# OPBS-Dynamo.net
KiCad netlist of a schematic drawn in EAGLE
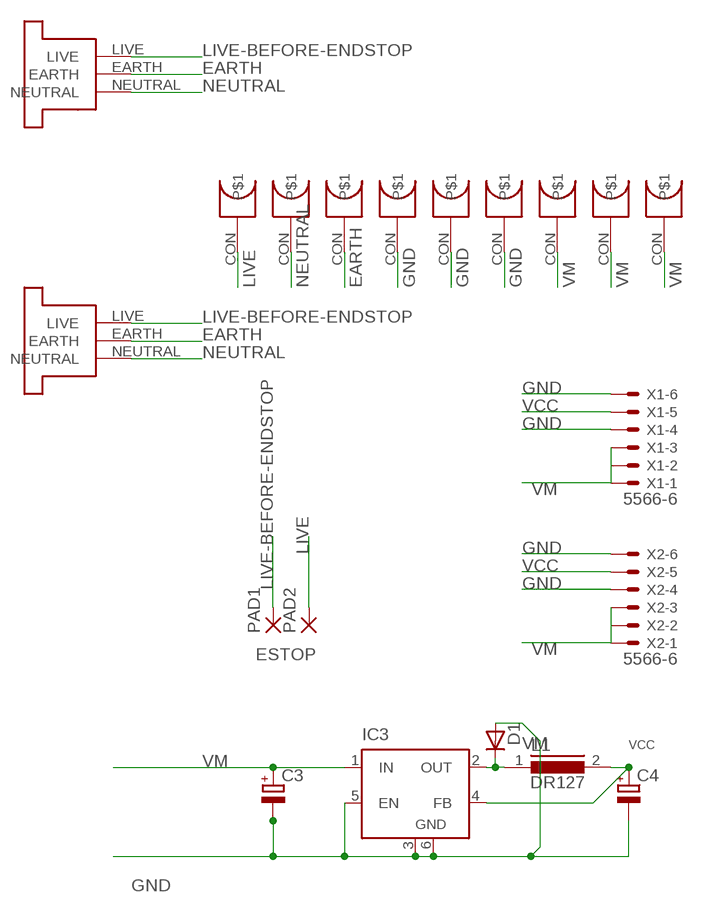
[diagram p0: schematic, sheet 1]

(export (version "E")
  (design (tool "Eeschema 10.0.6"))
  (components
    (comp (ref "C3")
      (value "CPOL-EUE")
      (footprint "eagle-import:PANASONIC_E")
      (libsource (lib "eagle-import") (part "CPOL-EUE"))
    )
    (comp (ref "C4")
      (value "CPOL-EUE")
      (footprint "eagle-import:PANASONIC_E")
      (libsource (lib "eagle-import") (part "CPOL-EUE"))
    )
    (comp (ref "D1")
      (value "D-SOD-87")
      (footprint "eagle-import:SOD87")
      (libsource (lib "eagle-import") (part "D-SOD-87"))
    )
    (comp (ref "EARTH")
      (value "SLIDEINSCREW9.53")
      (footprint "eagle-import:SLIDEINSCREW")
      (libsource (lib "eagle-import") (part "SLIDEINSCREW9.53"))
    )
    (comp (ref "GND1")
      (value "SLIDEINSCREW9.53")
      (footprint "eagle-import:SLIDEINSCREW")
      (libsource (lib "eagle-import") (part "SLIDEINSCREW9.53"))
    )
    (comp (ref "GND2")
      (value "SLIDEINSCREW9.53")
      (footprint "eagle-import:SLIDEINSCREW")
      (libsource (lib "eagle-import") (part "SLIDEINSCREW9.53"))
    )
    (comp (ref "GND3")
      (value "SLIDEINSCREW9.53")
      (footprint "eagle-import:SLIDEINSCREW")
      (libsource (lib "eagle-import") (part "SLIDEINSCREW9.53"))
    )
    (comp (ref "IC3")
      (value "LM2596S")
      (footprint "eagle-import:TO263-5")
      (libsource (lib "eagle-import") (part "LM2596S"))
    )
    (comp (ref "L1")
      (value "DR127")
      (footprint "eagle-import:DR127")
      (libsource (lib "eagle-import") (part "DR127"))
    )
    (comp (ref "LIVE")
      (value "SLIDEINSCREW9.53")
      (footprint "eagle-import:SLIDEINSCREW")
      (libsource (lib "eagle-import") (part "SLIDEINSCREW9.53"))
    )
    (comp (ref "NEUTRAL")
      (value "SLIDEINSCREW9.53")
      (footprint "eagle-import:SLIDEINSCREW")
      (libsource (lib "eagle-import") (part "SLIDEINSCREW9.53"))
    )
    (comp (ref "PAD1")
      (value "3,81/1,4")
      (footprint "eagle-import:3,81_1,4")
      (libsource (lib "eagle-import") (part "3,81/1,4"))
    )
    (comp (ref "PAD2")
      (value "3,81/1,4")
      (footprint "eagle-import:3,81_1,4")
      (libsource (lib "eagle-import") (part "3,81/1,4"))
    )
    (comp (ref "U$1")
      (value "IEC320JR-101S")
      (footprint "eagle-import:IEC320-JR101S")
      (libsource (lib "eagle-import") (part "IEC320JR-101S"))
    )
    (comp (ref "U$2")
      (value "IEC320JR-101S")
      (footprint "eagle-import:IEC320-JR101S")
      (libsource (lib "eagle-import") (part "IEC320JR-101S"))
    )
    (comp (ref "V1")
      (value "SLIDEINSCREW9.53")
      (footprint "eagle-import:SLIDEINSCREW")
      (libsource (lib "eagle-import") (part "SLIDEINSCREW9.53"))
    )
    (comp (ref "V2")
      (value "SLIDEINSCREW9.53")
      (footprint "eagle-import:SLIDEINSCREW")
      (libsource (lib "eagle-import") (part "SLIDEINSCREW9.53"))
    )
    (comp (ref "V3")
      (value "SLIDEINSCREW9.53")
      (footprint "eagle-import:SLIDEINSCREW")
      (libsource (lib "eagle-import") (part "SLIDEINSCREW9.53"))
    )
    (comp (ref "X1")
      (value "5566-6")
      (footprint "eagle-import:5566-6")
      (fields (field (name "MPN") "95566-61002"))
      (libsource (lib "eagle-import") (part "5566-6"))
    )
    (comp (ref "X2")
      (value "5566-6")
      (footprint "eagle-import:5566-6")
      (fields (field (name "MPN") "95566-61002"))
      (libsource (lib "eagle-import") (part "5566-6"))
    )
  )
  (nets
    (net (code "1") (name "/EARTH") (class "Default")
      (node (ref "EARTH") (pin "CON") (pinfunction "P$1_CON") (pintype "bidirectional"))
      (node (ref "U$1") (pin "EARTH") (pinfunction "EARTH_EARTH") (pintype "bidirectional"))
      (node (ref "U$2") (pin "EARTH") (pinfunction "EARTH_EARTH") (pintype "bidirectional"))
    )
    (net (code "2") (name "/GND") (class "Default")
      (node (ref "C3") (pin "-") (pinfunction "-_-") (pintype "passive"))
      (node (ref "C4") (pin "-") (pinfunction "-_-") (pintype "passive"))
      (node (ref "D1") (pin "2") (pinfunction "A_2") (pintype "passive"))
      (node (ref "GND1") (pin "CON") (pinfunction "P$1_CON") (pintype "bidirectional"))
      (node (ref "GND2") (pin "CON") (pinfunction "P$1_CON") (pintype "bidirectional"))
      (node (ref "GND3") (pin "CON") (pinfunction "P$1_CON") (pintype "bidirectional"))
      (node (ref "IC3") (pin "3") (pinfunction "GND_3") (pintype "power_in"))
      (node (ref "IC3") (pin "5") (pinfunction "EN_5") (pintype "input"))
      (node (ref "IC3") (pin "6") (pinfunction "GND_6") (pintype "power_in"))
      (node (ref "X1") (pin "4") (pinfunction "S_4") (pintype "passive"))
      (node (ref "X1") (pin "6") (pinfunction "S_6") (pintype "passive"))
      (node (ref "X2") (pin "4") (pinfunction "S_4") (pintype "passive"))
      (node (ref "X2") (pin "6") (pinfunction "S_6") (pintype "passive"))
    )
    (net (code "3") (name "/LIVE") (class "Default")
      (node (ref "LIVE") (pin "CON") (pinfunction "P$1_CON") (pintype "bidirectional"))
      (node (ref "PAD2") (pin "1") (pinfunction "P_1") (pintype "passive"))
    )
    (net (code "4") (name "/LIVE-BEFORE-ENDSTOP") (class "Default")
      (node (ref "PAD1") (pin "1") (pinfunction "P_1") (pintype "passive"))
      (node (ref "U$1") (pin "LIVE") (pinfunction "LIVE_LIVE") (pintype "bidirectional"))
      (node (ref "U$2") (pin "LIVE") (pinfunction "LIVE_LIVE") (pintype "bidirectional"))
    )
    (net (code "5") (name "/NEUTRAL") (class "Default")
      (node (ref "NEUTRAL") (pin "CON") (pinfunction "P$1_CON") (pintype "bidirectional"))
      (node (ref "U$1") (pin "NEUTRAL") (pinfunction "NEUTRAL_NEUTRAL") (pintype "bidirectional"))
      (node (ref "U$2") (pin "NEUTRAL") (pinfunction "NEUTRAL_NEUTRAL") (pintype "bidirectional"))
    )
    (net (code "6") (name "/VCC") (class "Default")
      (node (ref "C4") (pin "+") (pinfunction "+_+") (pintype "passive"))
      (node (ref "IC3") (pin "4") (pinfunction "FB_4") (pintype "input"))
      (node (ref "L1") (pin "2") (pinfunction "2_2") (pintype "passive"))
      (node (ref "X1") (pin "5") (pinfunction "S_5") (pintype "passive"))
      (node (ref "X2") (pin "5") (pinfunction "S_5") (pintype "passive"))
    )
    (net (code "7") (name "/VM") (class "Default")
      (node (ref "C3") (pin "+") (pinfunction "+_+") (pintype "passive"))
      (node (ref "IC3") (pin "1") (pinfunction "IN_1") (pintype "input"))
      (node (ref "V1") (pin "CON") (pinfunction "P$1_CON") (pintype "bidirectional"))
      (node (ref "V2") (pin "CON") (pinfunction "P$1_CON") (pintype "bidirectional"))
      (node (ref "V3") (pin "CON") (pinfunction "P$1_CON") (pintype "bidirectional"))
      (node (ref "X1") (pin "1") (pinfunction "S_1") (pintype "passive"))
      (node (ref "X1") (pin "2") (pinfunction "S_2") (pintype "passive"))
      (node (ref "X1") (pin "3") (pinfunction "S_3") (pintype "passive"))
      (node (ref "X2") (pin "1") (pinfunction "S_1") (pintype "passive"))
      (node (ref "X2") (pin "2") (pinfunction "S_2") (pintype "passive"))
      (node (ref "X2") (pin "3") (pinfunction "S_3") (pintype "passive"))
    )
    (net (code "8") (name "Net-(D1-C)") (class "Default")
      (node (ref "D1") (pin "1") (pinfunction "C_1") (pintype "passive"))
      (node (ref "IC3") (pin "2") (pinfunction "OUT_2") (pintype "output"))
      (node (ref "L1") (pin "1") (pinfunction "1_1") (pintype "passive"))
    )
  )
)
